# simple-loop-vrs.net
KiCad netlist of a schematic drawn in EAGLE
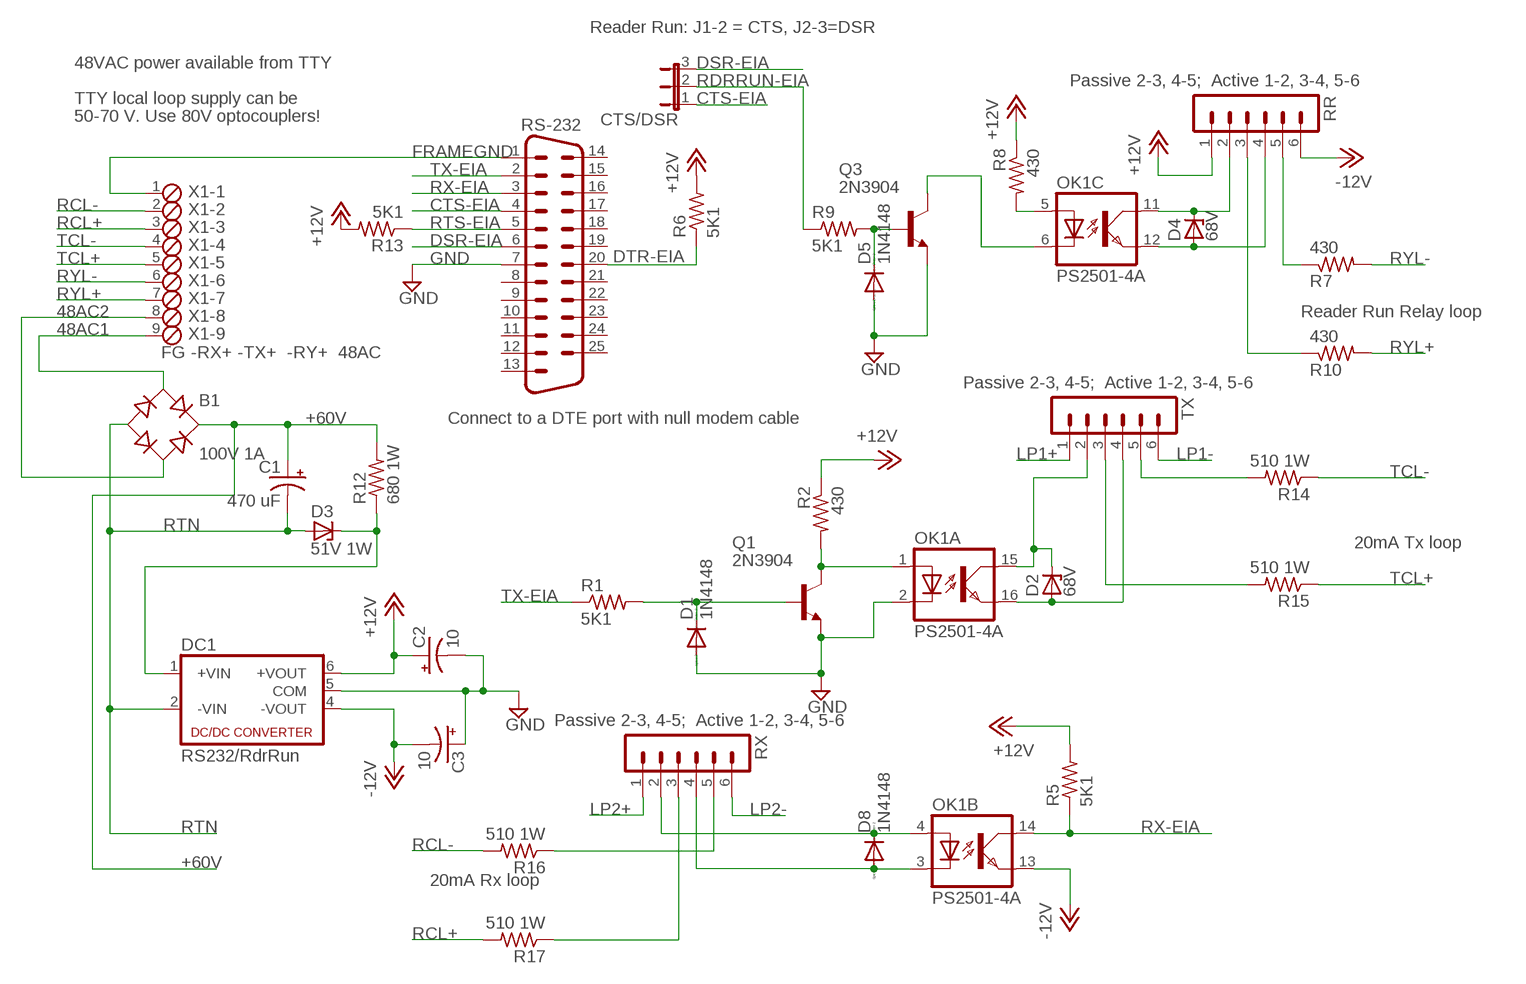
[diagram p0: schematic, sheet 1]
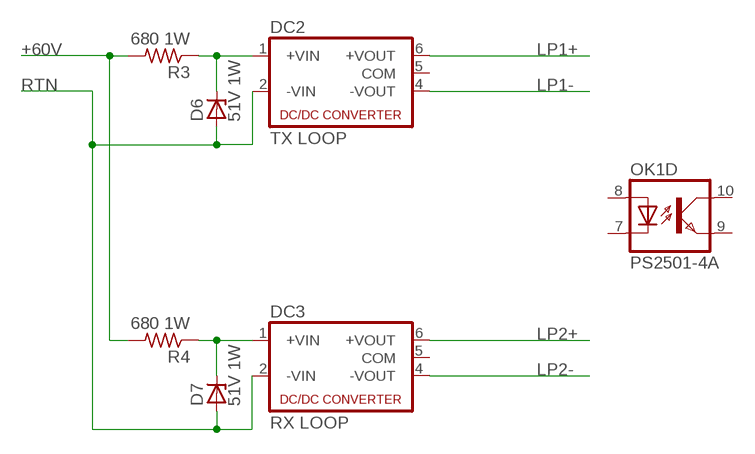
[diagram p1: schematic, sheet 2]

(export (version "E")
  (design (tool "Eeschema 10.0.6"))
  (components
    (comp (ref "D6")
      (value "51V 1W")
      (footprint "eagle-import:DO41Z10")
      (libsource (lib "eagle-import") (part "ZENER-DIODEDO41Z10"))
    )
    (comp (ref "D7")
      (value "51V 1W")
      (footprint "eagle-import:DO41Z10")
      (libsource (lib "eagle-import") (part "ZENER-DIODEDO41Z10"))
    )
    (comp (ref "DC2")
      (value "TX LOOP")
      (footprint "eagle-import:NMA")
      (fields (field (name "MF") "C & D TECHNOLOGIES, INC") (field (name "MPN") "NMA0515SC"))
      (libsource (lib "eagle-import") (part "NMA"))
    )
    (comp (ref "DC3")
      (value "RX LOOP")
      (footprint "eagle-import:NMA")
      (fields (field (name "MF") "C & D TECHNOLOGIES, INC") (field (name "MPN") "NMA0515SC"))
      (libsource (lib "eagle-import") (part "NMA"))
    )
    (comp (ref "OK1")
      (value "PS2501-4A")
      (footprint "eagle-import:DIL16")
      (fields (field (name "MF") "VISHAY/TELEFUNKEN") (field (name "MPN") "ILQ1"))
      (libsource (lib "eagle-import") (part "ILQ1"))
    )
    (comp (ref "R3")
      (value "680 1W")
      (footprint "eagle-import:P0817V")
      (libsource (lib "eagle-import") (part "R-US_0817/7V"))
    )
    (comp (ref "R4")
      (value "680 1W")
      (footprint "eagle-import:P0817V")
      (libsource (lib "eagle-import") (part "R-US_0817/7V"))
    )
    (comp (ref "B1")
      (value "100V 1A")
      (footprint "eagle-import:RB1A")
      (libsource (lib "eagle-import") (part "RB1A"))
    )
    (comp (ref "C1")
      (value "470 uF")
      (footprint "eagle-import:E7,5-18")
      (libsource (lib "eagle-import") (part "CPOL-USE7.5-18"))
    )
    (comp (ref "C2")
      (value "10")
      (footprint "eagle-import:B45181A")
      (libsource (lib "eagle-import") (part "CPOL-USB45181A"))
    )
    (comp (ref "C3")
      (value "10")
      (footprint "eagle-import:B45181A")
      (libsource (lib "eagle-import") (part "CPOL-USB45181A"))
    )
    (comp (ref "CTS/DSR")
      (value "JP2E")
      (footprint "eagle-import:JP2")
      (libsource (lib "eagle-import") (part "JP2E"))
    )
    (comp (ref "D1")
      (value "1N4148")
      (footprint "eagle-import:DO35-10")
      (libsource (lib "eagle-import") (part "1N4148DO35-10"))
    )
    (comp (ref "D2")
      (value "68V")
      (footprint "eagle-import:DO41Z10")
      (libsource (lib "eagle-import") (part "ZENER-DIODEDO41Z10"))
    )
    (comp (ref "D3")
      (value "51V 1W")
      (footprint "eagle-import:DO41Z10")
      (libsource (lib "eagle-import") (part "ZENER-DIODEDO41Z10"))
    )
    (comp (ref "D4")
      (value "68V")
      (footprint "eagle-import:DO41Z10")
      (libsource (lib "eagle-import") (part "ZENER-DIODEDO41Z10"))
    )
    (comp (ref "D5")
      (value "1N4148")
      (footprint "eagle-import:DO35-10")
      (libsource (lib "eagle-import") (part "1N4148DO35-10"))
    )
    (comp (ref "D8")
      (value "1N4148")
      (footprint "eagle-import:DO35-10")
      (libsource (lib "eagle-import") (part "1N4148DO35-10"))
    )
    (comp (ref "DC1")
      (value "RS232/RdrRun")
      (footprint "eagle-import:NMA")
      (fields (field (name "MF") "C & D TECHNOLOGIES, INC") (field (name "MPN") "NMA0515SC"))
      (libsource (lib "eagle-import") (part "NMA"))
    )
    (comp (ref "Q1")
      (value "2N3904")
      (footprint "eagle-import:TO92")
      (libsource (lib "eagle-import") (part "2N3904"))
    )
    (comp (ref "Q3")
      (value "2N3904")
      (footprint "eagle-import:TO92")
      (libsource (lib "eagle-import") (part "2N3904"))
    )
    (comp (ref "R1")
      (value "5K1")
      (footprint "eagle-import:0207_10")
      (libsource (lib "eagle-import") (part "R-US_0207/10"))
    )
    (comp (ref "R2")
      (value "430")
      (footprint "eagle-import:0207_10")
      (libsource (lib "eagle-import") (part "R-US_0207/10"))
    )
    (comp (ref "R5")
      (value "5K1")
      (footprint "eagle-import:0207_10")
      (libsource (lib "eagle-import") (part "R-US_0207/10"))
    )
    (comp (ref "R6")
      (value "5K1")
      (footprint "eagle-import:0207_10")
      (libsource (lib "eagle-import") (part "R-US_0207/10"))
    )
    (comp (ref "R7")
      (value "430")
      (footprint "eagle-import:0207_10")
      (libsource (lib "eagle-import") (part "R-US_0207/10"))
    )
    (comp (ref "R8")
      (value "430")
      (footprint "eagle-import:0207_10")
      (libsource (lib "eagle-import") (part "R-US_0207/10"))
    )
    (comp (ref "R9")
      (value "5K1")
      (footprint "eagle-import:0207_10")
      (libsource (lib "eagle-import") (part "R-US_0207/10"))
    )
    (comp (ref "R10")
      (value "430")
      (footprint "eagle-import:0207_10")
      (libsource (lib "eagle-import") (part "R-US_0207/10"))
    )
    (comp (ref "R12")
      (value "680 1W")
      (footprint "eagle-import:P0817V")
      (libsource (lib "eagle-import") (part "R-US_0817/7V"))
    )
    (comp (ref "R13")
      (value "5K1")
      (footprint "eagle-import:0207_10")
      (libsource (lib "eagle-import") (part "R-US_0207/10"))
    )
    (comp (ref "R14")
      (value "510 1W")
      (footprint "eagle-import:P0817V")
      (libsource (lib "eagle-import") (part "R-US_0817/7V"))
    )
    (comp (ref "R15")
      (value "510 1W")
      (footprint "eagle-import:P0817V")
      (libsource (lib "eagle-import") (part "R-US_0817/7V"))
    )
    (comp (ref "R16")
      (value "510 1W")
      (footprint "eagle-import:P0817V")
      (libsource (lib "eagle-import") (part "R-US_0817/7V"))
    )
    (comp (ref "R17")
      (value "510 1W")
      (footprint "eagle-import:P0817V")
      (libsource (lib "eagle-import") (part "R-US_0817/7V"))
    )
    (comp (ref "RR")
      (value "MA06-1")
      (footprint "eagle-import:MA06-1")
      (libsource (lib "eagle-import") (part "MA06-1"))
    )
    (comp (ref "RS-232")
      (value "M25H")
      (footprint "eagle-import:M25H")
      (libsource (lib "eagle-import") (part "M25H"))
    )
    (comp (ref "RX")
      (value "MA06-1")
      (footprint "eagle-import:MA06-1")
      (libsource (lib "eagle-import") (part "MA06-1"))
    )
    (comp (ref "TX")
      (value "MA06-1")
      (footprint "eagle-import:MA06-1")
      (libsource (lib "eagle-import") (part "MA06-1"))
    )
    (comp (ref "X1")
      (value "FG -RX+ -TX+ -RY+ 48AC")
      (footprint "eagle-import:9POL254")
      (libsource (lib "eagle-import") (part "MPT9"))
    )
  )
  (nets
    (net (code "1") (name "+12V") (class "Default")
      (node (ref "C2") (pin "+") (pinfunction "+_+") (pintype "passive"))
      (node (ref "DC1") (pin "6") (pinfunction "+VOUT_6") (pintype "passive"))
      (node (ref "R13") (pin "2") (pinfunction "2_2") (pintype "passive"))
      (node (ref "R2") (pin "1") (pinfunction "1_1") (pintype "passive"))
      (node (ref "R5") (pin "2") (pinfunction "2_2") (pintype "passive"))
      (node (ref "R6") (pin "2") (pinfunction "2_2") (pintype "passive"))
      (node (ref "R8") (pin "1") (pinfunction "1_1") (pintype "passive"))
      (node (ref "RR") (pin "1") (pinfunction "1_1") (pintype "passive"))
    )
    (net (code "2") (name "+60V") (class "Default")
      (node (ref "B1") (pin "+") (pinfunction "+_+") (pintype "passive"))
      (node (ref "C1") (pin "+") (pinfunction "+_+") (pintype "passive"))
      (node (ref "R12") (pin "2") (pinfunction "2_2") (pintype "passive"))
      (node (ref "R3") (pin "2") (pinfunction "2_2") (pintype "passive"))
      (node (ref "R4") (pin "2") (pinfunction "2_2") (pintype "passive"))
    )
    (net (code "3") (name "-12V") (class "Default")
      (node (ref "C3") (pin "-") (pinfunction "-_-") (pintype "passive"))
      (node (ref "DC1") (pin "4") (pinfunction "-VOUT_4") (pintype "passive"))
      (node (ref "OK1") (pin "13") (pinfunction "EMIT_13") (pintype "passive"))
      (node (ref "RR") (pin "6") (pinfunction "6_6") (pintype "passive"))
    )
    (net (code "4") (name "48AC1") (class "Default")
      (node (ref "B1") (pin "AC1") (pinfunction "AC1_AC1") (pintype "passive"))
      (node (ref "X1") (pin "9") (pinfunction "1_9") (pintype "passive"))
    )
    (net (code "5") (name "48AC2") (class "Default")
      (node (ref "B1") (pin "AC2") (pinfunction "AC2_AC2") (pintype "passive"))
      (node (ref "X1") (pin "8") (pinfunction "1_8") (pintype "passive"))
    )
    (net (code "6") (name "CTS-EIA") (class "Default")
      (node (ref "CTS/DSR") (pin "1") (pinfunction "1_1") (pintype "passive"))
      (node (ref "RS-232") (pin "4") (pinfunction "4_4") (pintype "passive"))
    )
    (net (code "7") (name "DSR-EIA") (class "Default")
      (node (ref "CTS/DSR") (pin "3") (pinfunction "3_3") (pintype "passive"))
      (node (ref "RS-232") (pin "6") (pinfunction "6_6") (pintype "passive"))
    )
    (net (code "8") (name "DTR-EIA") (class "Default")
      (node (ref "R6") (pin "1") (pinfunction "1_1") (pintype "passive"))
      (node (ref "RS-232") (pin "20") (pinfunction "20_20") (pintype "passive"))
    )
    (net (code "9") (name "FRAMEGND") (class "Default")
      (node (ref "RS-232") (pin "1") (pinfunction "1_1") (pintype "passive"))
      (node (ref "X1") (pin "1") (pinfunction "1_1") (pintype "passive"))
    )
    (net (code "10") (name "GND") (class "Default")
      (node (ref "C2") (pin "-") (pinfunction "-_-") (pintype "passive"))
      (node (ref "C3") (pin "+") (pinfunction "+_+") (pintype "passive"))
      (node (ref "D1") (pin "A") (pinfunction "A_A") (pintype "passive"))
      (node (ref "D5") (pin "A") (pinfunction "A_A") (pintype "passive"))
      (node (ref "DC1") (pin "5") (pinfunction "COM_5") (pintype "passive"))
      (node (ref "OK1") (pin "2") (pinfunction "C_2") (pintype "passive"))
      (node (ref "Q1") (pin "3") (pinfunction "E_3") (pintype "passive"))
      (node (ref "Q3") (pin "3") (pinfunction "E_3") (pintype "passive"))
      (node (ref "RS-232") (pin "7") (pinfunction "7_7") (pintype "passive"))
    )
    (net (code "11") (name "LP1+") (class "Default")
      (node (ref "DC2") (pin "6") (pinfunction "+VOUT_6") (pintype "passive"))
      (node (ref "TX") (pin "1") (pinfunction "1_1") (pintype "passive"))
    )
    (net (code "12") (name "LP1-") (class "Default")
      (node (ref "DC2") (pin "4") (pinfunction "-VOUT_4") (pintype "passive"))
      (node (ref "TX") (pin "6") (pinfunction "6_6") (pintype "passive"))
    )
    (net (code "13") (name "LP2+") (class "Default")
      (node (ref "DC3") (pin "6") (pinfunction "+VOUT_6") (pintype "passive"))
      (node (ref "RX") (pin "1") (pinfunction "1_1") (pintype "passive"))
    )
    (net (code "14") (name "LP2-") (class "Default")
      (node (ref "DC3") (pin "4") (pinfunction "-VOUT_4") (pintype "passive"))
      (node (ref "RX") (pin "6") (pinfunction "6_6") (pintype "passive"))
    )
    (net (code "15") (name "Net-(DC1-+VIN)") (class "Default")
      (node (ref "D3") (pin "C") (pinfunction "C_C") (pintype "passive"))
      (node (ref "DC1") (pin "1") (pinfunction "+VIN_1") (pintype "passive"))
      (node (ref "R12") (pin "1") (pinfunction "1_1") (pintype "passive"))
    )
    (net (code "16") (name "Net-(DC2-+VIN)") (class "Default")
      (node (ref "D6") (pin "C") (pinfunction "C_C") (pintype "passive"))
      (node (ref "DC2") (pin "1") (pinfunction "+VIN_1") (pintype "passive"))
      (node (ref "R3") (pin "1") (pinfunction "1_1") (pintype "passive"))
    )
    (net (code "17") (name "Net-(DC3-+VIN)") (class "Default")
      (node (ref "D7") (pin "C") (pinfunction "C_C") (pintype "passive"))
      (node (ref "DC3") (pin "1") (pinfunction "+VIN_1") (pintype "passive"))
      (node (ref "R4") (pin "1") (pinfunction "1_1") (pintype "passive"))
    )
    (net (code "18") (name "Net-(OK1A-A)") (class "Default")
      (node (ref "OK1") (pin "1") (pinfunction "A_1") (pintype "passive"))
      (node (ref "Q1") (pin "1") (pinfunction "C_1") (pintype "passive"))
      (node (ref "R2") (pin "2") (pinfunction "2_2") (pintype "passive"))
    )
    (net (code "19") (name "Net-(OK1A-COL)") (class "Default")
      (node (ref "D2") (pin "C") (pinfunction "C_C") (pintype "passive"))
      (node (ref "OK1") (pin "15") (pinfunction "COL_15") (pintype "passive"))
      (node (ref "TX") (pin "2") (pinfunction "2_2") (pintype "passive"))
    )
    (net (code "20") (name "Net-(OK1A-EMIT)") (class "Default")
      (node (ref "D2") (pin "A") (pinfunction "A_A") (pintype "passive"))
      (node (ref "OK1") (pin "16") (pinfunction "EMIT_16") (pintype "passive"))
      (node (ref "TX") (pin "4") (pinfunction "4_4") (pintype "passive"))
    )
    (net (code "21") (name "Net-(OK1B-A)") (class "Default")
      (node (ref "D8") (pin "C") (pinfunction "C_C") (pintype "passive"))
      (node (ref "OK1") (pin "4") (pinfunction "A_4") (pintype "passive"))
      (node (ref "RX") (pin "2") (pinfunction "2_2") (pintype "passive"))
    )
    (net (code "22") (name "Net-(OK1B-C)") (class "Default")
      (node (ref "D8") (pin "A") (pinfunction "A_A") (pintype "passive"))
      (node (ref "OK1") (pin "3") (pinfunction "C_3") (pintype "passive"))
      (node (ref "RX") (pin "4") (pinfunction "4_4") (pintype "passive"))
    )
    (net (code "23") (name "Net-(OK1C-A)") (class "Default")
      (node (ref "OK1") (pin "5") (pinfunction "A_5") (pintype "passive"))
      (node (ref "R8") (pin "2") (pinfunction "2_2") (pintype "passive"))
    )
    (net (code "24") (name "Net-(OK1C-C)") (class "Default")
      (node (ref "OK1") (pin "6") (pinfunction "C_6") (pintype "passive"))
      (node (ref "Q3") (pin "1") (pinfunction "C_1") (pintype "passive"))
    )
    (net (code "25") (name "Net-(OK1C-COL)") (class "Default")
      (node (ref "D4") (pin "C") (pinfunction "C_C") (pintype "passive"))
      (node (ref "OK1") (pin "11") (pinfunction "COL_11") (pintype "passive"))
      (node (ref "RR") (pin "2") (pinfunction "2_2") (pintype "passive"))
    )
    (net (code "26") (name "Net-(OK1C-EMIT)") (class "Default")
      (node (ref "D4") (pin "A") (pinfunction "A_A") (pintype "passive"))
      (node (ref "OK1") (pin "12") (pinfunction "EMIT_12") (pintype "passive"))
      (node (ref "RR") (pin "4") (pinfunction "4_4") (pintype "passive"))
    )
    (net (code "27") (name "Net-(Q1-B)") (class "Default")
      (node (ref "D1") (pin "C") (pinfunction "C_C") (pintype "passive"))
      (node (ref "Q1") (pin "2") (pinfunction "B_2") (pintype "passive"))
      (node (ref "R1") (pin "2") (pinfunction "2_2") (pintype "passive"))
    )
    (net (code "28") (name "Net-(Q3-B)") (class "Default")
      (node (ref "D5") (pin "C") (pinfunction "C_C") (pintype "passive"))
      (node (ref "Q3") (pin "2") (pinfunction "B_2") (pintype "passive"))
      (node (ref "R9") (pin "2") (pinfunction "2_2") (pintype "passive"))
    )
    (net (code "29") (name "Net-(R7-Pad1)") (class "Default")
      (node (ref "R7") (pin "1") (pinfunction "1_1") (pintype "passive"))
      (node (ref "RR") (pin "5") (pinfunction "5_5") (pintype "passive"))
    )
    (net (code "30") (name "Net-(R10-Pad1)") (class "Default")
      (node (ref "R10") (pin "1") (pinfunction "1_1") (pintype "passive"))
      (node (ref "RR") (pin "3") (pinfunction "3_3") (pintype "passive"))
    )
    (net (code "31") (name "Net-(R14-Pad2)") (class "Default")
      (node (ref "R14") (pin "2") (pinfunction "2_2") (pintype "passive"))
      (node (ref "TX") (pin "5") (pinfunction "5_5") (pintype "passive"))
    )
    (net (code "32") (name "Net-(R15-Pad2)") (class "Default")
      (node (ref "R15") (pin "2") (pinfunction "2_2") (pintype "passive"))
      (node (ref "TX") (pin "3") (pinfunction "3_3") (pintype "passive"))
    )
    (net (code "33") (name "Net-(R16-Pad1)") (class "Default")
      (node (ref "R16") (pin "1") (pinfunction "1_1") (pintype "passive"))
      (node (ref "RX") (pin "5") (pinfunction "5_5") (pintype "passive"))
    )
    (net (code "34") (name "Net-(R17-Pad1)") (class "Default")
      (node (ref "R17") (pin "1") (pinfunction "1_1") (pintype "passive"))
      (node (ref "RX") (pin "3") (pinfunction "3_3") (pintype "passive"))
    )
    (net (code "35") (name "RCL+") (class "Default")
      (node (ref "R17") (pin "2") (pinfunction "2_2") (pintype "passive"))
      (node (ref "X1") (pin "3") (pinfunction "1_3") (pintype "passive"))
    )
    (net (code "36") (name "RCL-") (class "Default")
      (node (ref "R16") (pin "2") (pinfunction "2_2") (pintype "passive"))
      (node (ref "X1") (pin "2") (pinfunction "1_2") (pintype "passive"))
    )
    (net (code "37") (name "RDRRUN-EIA") (class "Default")
      (node (ref "CTS/DSR") (pin "2") (pinfunction "2_2") (pintype "passive"))
      (node (ref "R9") (pin "1") (pinfunction "1_1") (pintype "passive"))
    )
    (net (code "38") (name "RTN") (class "Default")
      (node (ref "B1") (pin "-") (pinfunction "-_-") (pintype "passive"))
      (node (ref "C1") (pin "-") (pinfunction "-_-") (pintype "passive"))
      (node (ref "D3") (pin "A") (pinfunction "A_A") (pintype "passive"))
      (node (ref "D6") (pin "A") (pinfunction "A_A") (pintype "passive"))
      (node (ref "D7") (pin "A") (pinfunction "A_A") (pintype "passive"))
      (node (ref "DC1") (pin "2") (pinfunction "-VIN_2") (pintype "passive"))
      (node (ref "DC2") (pin "2") (pinfunction "-VIN_2") (pintype "passive"))
      (node (ref "DC3") (pin "2") (pinfunction "-VIN_2") (pintype "passive"))
    )
    (net (code "39") (name "RTS-EIA") (class "Default")
      (node (ref "R13") (pin "1") (pinfunction "1_1") (pintype "passive"))
      (node (ref "RS-232") (pin "5") (pinfunction "5_5") (pintype "passive"))
    )
    (net (code "40") (name "RX-EIA") (class "Default")
      (node (ref "OK1") (pin "14") (pinfunction "COL_14") (pintype "passive"))
      (node (ref "R5") (pin "1") (pinfunction "1_1") (pintype "passive"))
      (node (ref "RS-232") (pin "3") (pinfunction "3_3") (pintype "passive"))
    )
    (net (code "41") (name "RYL+") (class "Default")
      (node (ref "R10") (pin "2") (pinfunction "2_2") (pintype "passive"))
      (node (ref "X1") (pin "7") (pinfunction "1_7") (pintype "passive"))
    )
    (net (code "42") (name "RYL-") (class "Default")
      (node (ref "R7") (pin "2") (pinfunction "2_2") (pintype "passive"))
      (node (ref "X1") (pin "6") (pinfunction "1_6") (pintype "passive"))
    )
    (net (code "43") (name "TCL+") (class "Default")
      (node (ref "R15") (pin "1") (pinfunction "1_1") (pintype "passive"))
      (node (ref "X1") (pin "5") (pinfunction "1_5") (pintype "passive"))
    )
    (net (code "44") (name "TCL-") (class "Default")
      (node (ref "R14") (pin "1") (pinfunction "1_1") (pintype "passive"))
      (node (ref "X1") (pin "4") (pinfunction "1_4") (pintype "passive"))
    )
    (net (code "45") (name "TX-EIA") (class "Default")
      (node (ref "R1") (pin "1") (pinfunction "1_1") (pintype "passive"))
      (node (ref "RS-232") (pin "2") (pinfunction "2_2") (pintype "passive"))
    )
    (net (code "46") (name "unconnected-(DC2-COM-Pad5)") (class "Default")
      (node (ref "DC2") (pin "5") (pinfunction "COM_5") (pintype "passive"))
    )
    (net (code "47") (name "unconnected-(DC3-COM-Pad5)") (class "Default")
      (node (ref "DC3") (pin "5") (pinfunction "COM_5") (pintype "passive"))
    )
    (net (code "48") (name "unconnected-(OK1D-A-Pad8)") (class "Default")
      (node (ref "OK1") (pin "8") (pinfunction "A_8") (pintype "passive"))
    )
    (net (code "49") (name "unconnected-(OK1D-C-Pad7)") (class "Default")
      (node (ref "OK1") (pin "7") (pinfunction "C_7") (pintype "passive"))
    )
    (net (code "50") (name "unconnected-(OK1D-COL-Pad10)") (class "Default")
      (node (ref "OK1") (pin "10") (pinfunction "COL_10") (pintype "passive"))
    )
    (net (code "51") (name "unconnected-(OK1D-EMIT-Pad9)") (class "Default")
      (node (ref "OK1") (pin "9") (pinfunction "EMIT_9") (pintype "passive"))
    )
    (net (code "52") (name "unconnected-(RS-232-Pad8)") (class "Default")
      (node (ref "RS-232") (pin "8") (pinfunction "8_8") (pintype "passive"))
    )
    (net (code "53") (name "unconnected-(RS-232-Pad9)") (class "Default")
      (node (ref "RS-232") (pin "9") (pinfunction "9_9") (pintype "passive"))
    )
    (net (code "54") (name "unconnected-(RS-232-Pad10)") (class "Default")
      (node (ref "RS-232") (pin "10") (pinfunction "10_10") (pintype "passive"))
    )
    (net (code "55") (name "unconnected-(RS-232-Pad11)") (class "Default")
      (node (ref "RS-232") (pin "11") (pinfunction "11_11") (pintype "passive"))
    )
    (net (code "56") (name "unconnected-(RS-232-Pad12)") (class "Default")
      (node (ref "RS-232") (pin "12") (pinfunction "12_12") (pintype "passive"))
    )
    (net (code "57") (name "unconnected-(RS-232-Pad13)") (class "Default")
      (node (ref "RS-232") (pin "13") (pinfunction "13_13") (pintype "passive"))
    )
    (net (code "58") (name "unconnected-(RS-232-Pad14)") (class "Default")
      (node (ref "RS-232") (pin "14") (pinfunction "14_14") (pintype "passive"))
    )
    (net (code "59") (name "unconnected-(RS-232-Pad15)") (class "Default")
      (node (ref "RS-232") (pin "15") (pinfunction "15_15") (pintype "passive"))
    )
    (net (code "60") (name "unconnected-(RS-232-Pad16)") (class "Default")
      (node (ref "RS-232") (pin "16") (pinfunction "16_16") (pintype "passive"))
    )
    (net (code "61") (name "unconnected-(RS-232-Pad17)") (class "Default")
      (node (ref "RS-232") (pin "17") (pinfunction "17_17") (pintype "passive"))
    )
    (net (code "62") (name "unconnected-(RS-232-Pad18)") (class "Default")
      (node (ref "RS-232") (pin "18") (pinfunction "18_18") (pintype "passive"))
    )
    (net (code "63") (name "unconnected-(RS-232-Pad19)") (class "Default")
      (node (ref "RS-232") (pin "19") (pinfunction "19_19") (pintype "passive"))
    )
    (net (code "64") (name "unconnected-(RS-232-Pad21)") (class "Default")
      (node (ref "RS-232") (pin "21") (pinfunction "21_21") (pintype "passive"))
    )
    (net (code "65") (name "unconnected-(RS-232-Pad22)") (class "Default")
      (node (ref "RS-232") (pin "22") (pinfunction "22_22") (pintype "passive"))
    )
    (net (code "66") (name "unconnected-(RS-232-Pad23)") (class "Default")
      (node (ref "RS-232") (pin "23") (pinfunction "23_23") (pintype "passive"))
    )
    (net (code "67") (name "unconnected-(RS-232-Pad24)") (class "Default")
      (node (ref "RS-232") (pin "24") (pinfunction "24_24") (pintype "passive"))
    )
    (net (code "68") (name "unconnected-(RS-232-Pad25)") (class "Default")
      (node (ref "RS-232") (pin "25") (pinfunction "25_25") (pintype "passive"))
    )
  )
)
